# Halfshield.net
KiCad netlist of a schematic drawn in EAGLE
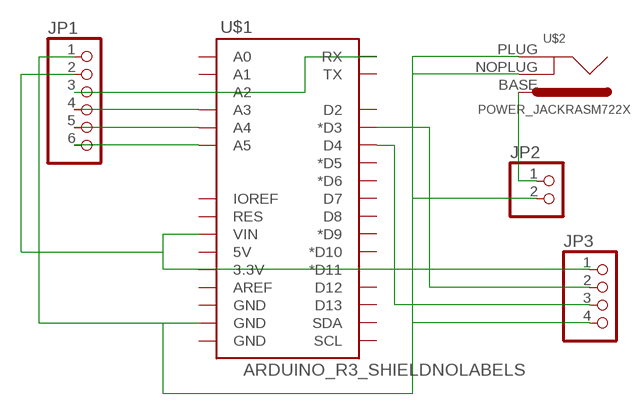
[diagram p0: schematic, sheet 1]

(export (version "E")
  (design (tool "Eeschema 10.0.6"))
  (components
    (comp (ref "JP1")
      (value "PINHD-1X6")
      (footprint "eagle-import:1X06")
      (libsource (lib "eagle-import") (part "PINHD-1X6"))
    )
    (comp (ref "JP2")
      (value "PINHD-1X2")
      (footprint "eagle-import:1X02")
      (libsource (lib "eagle-import") (part "PINHD-1X2"))
    )
    (comp (ref "JP3")
      (value "PINHD-1X4")
      (footprint "eagle-import:1X04")
      (libsource (lib "eagle-import") (part "PINHD-1X4"))
    )
    (comp (ref "U$1")
      (value "ARDUINO_R3_SHIELDNOLABELS")
      (footprint "eagle-import:UNO_R3_SHIELD_NOLABELS")
      (libsource (lib "eagle-import") (part "ARDUINO_R3_SHIELDNOLABELS"))
    )
    (comp (ref "U$2")
      (value "POWER_JACKRASM722X")
      (footprint "eagle-import:RASM722X")
      (libsource (lib "eagle-import") (part "POWER_JACKRASM722X"))
    )
  )
  (nets
    (net (code "1") (name "Net-(JP1-Pad2)") (class "Default")
      (node (ref "JP1") (pin "2") (pinfunction "2_2") (pintype "passive"))
      (node (ref "JP3") (pin "1") (pinfunction "1_1") (pintype "passive"))
      (node (ref "U$1") (pin "VIN") (pinfunction "VIN_VIN") (pintype "bidirectional"))
    )
    (net (code "2") (name "Net-(JP1-Pad3)") (class "Default")
      (node (ref "JP1") (pin "3") (pinfunction "3_3") (pintype "passive"))
      (node (ref "U$1") (pin "RX") (pinfunction "RX_RX") (pintype "bidirectional"))
    )
    (net (code "3") (name "Net-(JP1-Pad4)") (class "Default")
      (node (ref "JP1") (pin "4") (pinfunction "4_4") (pintype "passive"))
      (node (ref "U$1") (pin "A3") (pinfunction "A3_A3") (pintype "bidirectional"))
    )
    (net (code "4") (name "Net-(JP1-Pad5)") (class "Default")
      (node (ref "JP1") (pin "5") (pinfunction "5_5") (pintype "passive"))
      (node (ref "U$1") (pin "A4") (pinfunction "A4_A4") (pintype "bidirectional"))
    )
    (net (code "5") (name "Net-(JP1-Pad6)") (class "Default")
      (node (ref "JP1") (pin "6") (pinfunction "6_6") (pintype "passive"))
      (node (ref "U$1") (pin "A5") (pinfunction "A5_A5") (pintype "bidirectional"))
    )
    (net (code "6") (name "Net-(JP3-Pad3)") (class "Default")
      (node (ref "JP3") (pin "3") (pinfunction "3_3") (pintype "passive"))
      (node (ref "U$1") (pin "D4") (pinfunction "D4_D4") (pintype "bidirectional"))
    )
    (net (code "7") (name "Net-(U$1-*D3)") (class "Default")
      (node (ref "JP3") (pin "2") (pinfunction "2_2") (pintype "passive"))
      (node (ref "U$1") (pin "D3") (pinfunction "*D3_D3") (pintype "bidirectional"))
    )
    (net (code "8") (name "Net-(U$2-GND)") (class "Default")
      (node (ref "JP2") (pin "1") (pinfunction "1_1") (pintype "passive"))
      (node (ref "U$2") (pin "BASE") (pinfunction "GND_BASE") (pintype "bidirectional"))
    )
    (net (code "9") (name "Net-(U$2-OFF)") (class "Default")
      (node (ref "JP1") (pin "1") (pinfunction "1_1") (pintype "passive"))
      (node (ref "JP2") (pin "2") (pinfunction "2_2") (pintype "passive"))
      (node (ref "JP3") (pin "4") (pinfunction "4_4") (pintype "passive"))
      (node (ref "U$1") (pin "GND@1") (pinfunction "GND_GND@1") (pintype "bidirectional"))
      (node (ref "U$2") (pin "NOPLUG") (pinfunction "OFF_NOPLUG") (pintype "bidirectional"))
      (node (ref "U$2") (pin "PLUG") (pinfunction "ON_PLUG") (pintype "bidirectional"))
    )
    (net (code "10") (name "unconnected-(U$1-*D5-PadD5)") (class "Default")
      (node (ref "U$1") (pin "D5") (pinfunction "*D5_D5") (pintype "bidirectional"))
    )
    (net (code "11") (name "unconnected-(U$1-*D6-PadD6)") (class "Default")
      (node (ref "U$1") (pin "D6") (pinfunction "*D6_D6") (pintype "bidirectional"))
    )
    (net (code "12") (name "unconnected-(U$1-*D9-PadD9)") (class "Default")
      (node (ref "U$1") (pin "D9") (pinfunction "*D9_D9") (pintype "bidirectional"))
    )
    (net (code "13") (name "unconnected-(U$1-*D10-PadD10)") (class "Default")
      (node (ref "U$1") (pin "D10") (pinfunction "*D10_D10") (pintype "bidirectional"))
    )
    (net (code "14") (name "unconnected-(U$1-*D11-PadD11)") (class "Default")
      (node (ref "U$1") (pin "D11") (pinfunction "*D11_D11") (pintype "bidirectional"))
    )
    (net (code "15") (name "unconnected-(U$1-GND-PadGND@0)") (class "Default")
      (node (ref "U$1") (pin "GND@0") (pinfunction "GND_GND@0") (pintype "bidirectional"))
    )
    (net (code "16") (name "unconnected-(U$1-GND-PadGND@2)") (class "Default")
      (node (ref "U$1") (pin "GND@2") (pinfunction "GND_GND@2") (pintype "bidirectional"))
    )
    (net (code "17") (name "unconnected-(U$1-Pad3.3V)") (class "Default")
      (node (ref "U$1") (pin "3.3V") (pinfunction "3.3V_3.3V") (pintype "bidirectional"))
    )
    (net (code "18") (name "unconnected-(U$1-Pad5V)") (class "Default")
      (node (ref "U$1") (pin "5V") (pinfunction "5V_5V") (pintype "bidirectional"))
    )
    (net (code "19") (name "unconnected-(U$1-PadA0)") (class "Default")
      (node (ref "U$1") (pin "A0") (pinfunction "A0_A0") (pintype "bidirectional"))
    )
    (net (code "20") (name "unconnected-(U$1-PadA1)") (class "Default")
      (node (ref "U$1") (pin "A1") (pinfunction "A1_A1") (pintype "bidirectional"))
    )
    (net (code "21") (name "unconnected-(U$1-PadA2)") (class "Default")
      (node (ref "U$1") (pin "A2") (pinfunction "A2_A2") (pintype "bidirectional"))
    )
    (net (code "22") (name "unconnected-(U$1-PadAREF)") (class "Default")
      (node (ref "U$1") (pin "AREF") (pinfunction "AREF_AREF") (pintype "bidirectional"))
    )
    (net (code "23") (name "unconnected-(U$1-PadD2)") (class "Default")
      (node (ref "U$1") (pin "D2") (pinfunction "D2_D2") (pintype "bidirectional"))
    )
    (net (code "24") (name "unconnected-(U$1-PadD7)") (class "Default")
      (node (ref "U$1") (pin "D7") (pinfunction "D7_D7") (pintype "bidirectional"))
    )
    (net (code "25") (name "unconnected-(U$1-PadD8)") (class "Default")
      (node (ref "U$1") (pin "D8") (pinfunction "D8_D8") (pintype "bidirectional"))
    )
    (net (code "26") (name "unconnected-(U$1-PadD12)") (class "Default")
      (node (ref "U$1") (pin "D12") (pinfunction "D12_D12") (pintype "bidirectional"))
    )
    (net (code "27") (name "unconnected-(U$1-PadD13)") (class "Default")
      (node (ref "U$1") (pin "D13") (pinfunction "D13_D13") (pintype "bidirectional"))
    )
    (net (code "28") (name "unconnected-(U$1-PadIOREF)") (class "Default")
      (node (ref "U$1") (pin "IOREF") (pinfunction "IOREF_IOREF") (pintype "bidirectional"))
    )
    (net (code "29") (name "unconnected-(U$1-PadRES)") (class "Default")
      (node (ref "U$1") (pin "RES") (pinfunction "RES_RES") (pintype "bidirectional"))
    )
    (net (code "30") (name "unconnected-(U$1-PadSCL)") (class "Default")
      (node (ref "U$1") (pin "SCL") (pinfunction "SCL_SCL") (pintype "bidirectional"))
    )
    (net (code "31") (name "unconnected-(U$1-PadSDA)") (class "Default")
      (node (ref "U$1") (pin "SDA") (pinfunction "SDA_SDA") (pintype "bidirectional"))
    )
    (net (code "32") (name "unconnected-(U$1-PadTX)") (class "Default")
      (node (ref "U$1") (pin "TX") (pinfunction "TX_TX") (pintype "bidirectional"))
    )
  )
)
